# untitled.net
KiCad netlist of a schematic drawn in EAGLE
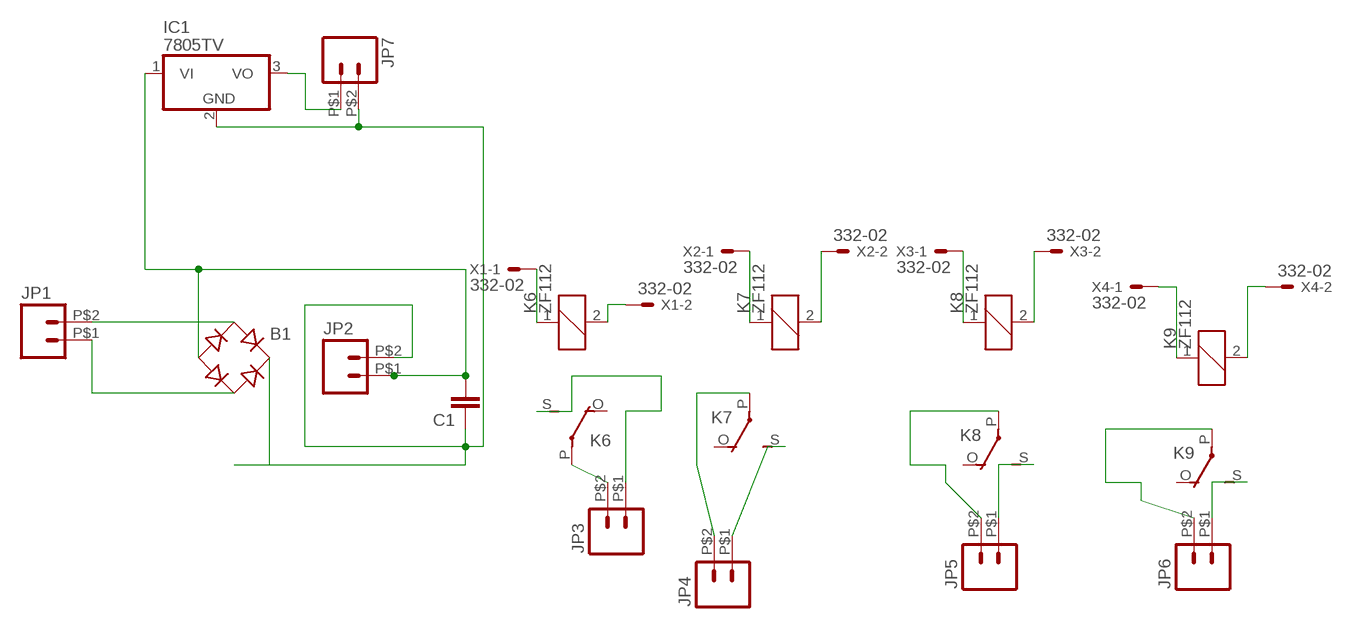
[diagram p0: schematic, sheet 1]

(export (version "E")
  (design (tool "Eeschema 10.0.6"))
  (components
    (comp (ref "B1")
      (value "RB1A")
      (footprint "eagle-import:RB1A")
      (libsource (lib "eagle-import") (part "RB1A"))
    )
    (comp (ref "C1")
      (value "CAPKIT")
      (footprint "eagle-import:CAP-PTH-SMALL-KIT")
      (libsource (lib "eagle-import") (part "CAPKIT"))
    )
    (comp (ref "IC1")
      (value "7805TV")
      (footprint "eagle-import:TO220V")
      (libsource (lib "eagle-import") (part "78TV05"))
    )
    (comp (ref "JP1")
      (value "M02PTH2")
      (footprint "eagle-import:1X02_BIG")
      (libsource (lib "eagle-import") (part "M02PTH2"))
    )
    (comp (ref "JP2")
      (value "M02PTH2")
      (footprint "eagle-import:1X02_BIG")
      (libsource (lib "eagle-import") (part "M02PTH2"))
    )
    (comp (ref "JP3")
      (value "M02PTH2")
      (footprint "eagle-import:1X02_BIG")
      (libsource (lib "eagle-import") (part "M02PTH2"))
    )
    (comp (ref "JP4")
      (value "M02PTH2")
      (footprint "eagle-import:1X02_BIG")
      (libsource (lib "eagle-import") (part "M02PTH2"))
    )
    (comp (ref "JP5")
      (value "M02PTH2")
      (footprint "eagle-import:1X02_BIG")
      (libsource (lib "eagle-import") (part "M02PTH2"))
    )
    (comp (ref "JP6")
      (value "M02PTH2")
      (footprint "eagle-import:1X02_BIG")
      (libsource (lib "eagle-import") (part "M02PTH2"))
    )
    (comp (ref "JP7")
      (value "M02PTH2")
      (footprint "eagle-import:1X02_BIG")
      (libsource (lib "eagle-import") (part "M02PTH2"))
    )
    (comp (ref "K6")
      (value "ZF112")
      (footprint "eagle-import:ZF112")
      (libsource (lib "eagle-import") (part "ZF112"))
    )
    (comp (ref "K7")
      (value "ZF112")
      (footprint "eagle-import:ZF112")
      (libsource (lib "eagle-import") (part "ZF112"))
    )
    (comp (ref "K8")
      (value "ZF112")
      (footprint "eagle-import:ZF112")
      (libsource (lib "eagle-import") (part "ZF112"))
    )
    (comp (ref "K9")
      (value "ZF112")
      (footprint "eagle-import:ZF112")
      (libsource (lib "eagle-import") (part "ZF112"))
    )
    (comp (ref "X1")
      (value "332-02")
      (footprint "eagle-import:332-02")
      (libsource (lib "eagle-import") (part "332-02"))
    )
    (comp (ref "X2")
      (value "332-02")
      (footprint "eagle-import:332-02")
      (libsource (lib "eagle-import") (part "332-02"))
    )
    (comp (ref "X3")
      (value "332-02")
      (footprint "eagle-import:332-02")
      (libsource (lib "eagle-import") (part "332-02"))
    )
    (comp (ref "X4")
      (value "332-02")
      (footprint "eagle-import:332-02")
      (libsource (lib "eagle-import") (part "332-02"))
    )
  )
  (nets
    (net (code "1") (name "Net-(IC1-GND)") (class "Default")
      (node (ref "B1") (pin "+") (pinfunction "+_+") (pintype "passive"))
      (node (ref "C1") (pin "1") (pinfunction "1_1") (pintype "passive"))
      (node (ref "IC1") (pin "2") (pinfunction "GND_2") (pintype "passive"))
      (node (ref "JP2") (pin "P$2") (pinfunction "2_P$2") (pintype "passive"))
      (node (ref "JP7") (pin "P$2") (pinfunction "2_P$2") (pintype "passive"))
    )
    (net (code "2") (name "Net-(IC1-VI)") (class "Default")
      (node (ref "B1") (pin "-") (pinfunction "-_-") (pintype "passive"))
      (node (ref "C1") (pin "2") (pinfunction "2_2") (pintype "passive"))
      (node (ref "IC1") (pin "1") (pinfunction "VI_1") (pintype "input"))
      (node (ref "JP2") (pin "P$1") (pinfunction "1_P$1") (pintype "passive"))
    )
    (net (code "3") (name "Net-(IC1-VO)") (class "Default")
      (node (ref "IC1") (pin "3") (pinfunction "VO_3") (pintype "passive"))
      (node (ref "JP7") (pin "P$1") (pinfunction "1_P$1") (pintype "passive"))
    )
    (net (code "4") (name "Net-(JP1-1)") (class "Default")
      (node (ref "B1") (pin "AC2") (pinfunction "AC2_AC2") (pintype "passive"))
      (node (ref "JP1") (pin "P$1") (pinfunction "1_P$1") (pintype "passive"))
    )
    (net (code "5") (name "Net-(JP1-2)") (class "Default")
      (node (ref "B1") (pin "AC1") (pinfunction "AC1_AC1") (pintype "passive"))
      (node (ref "JP1") (pin "P$2") (pinfunction "2_P$2") (pintype "passive"))
    )
    (net (code "6") (name "Net-(JP3-1)") (class "Default")
      (node (ref "JP3") (pin "P$1") (pinfunction "1_P$1") (pintype "passive"))
      (node (ref "K6") (pin "S") (pinfunction "S_S") (pintype "passive"))
    )
    (net (code "7") (name "Net-(JP3-2)") (class "Default")
      (node (ref "JP3") (pin "P$2") (pinfunction "2_P$2") (pintype "passive"))
      (node (ref "K6") (pin "P") (pinfunction "P_P") (pintype "passive"))
    )
    (net (code "8") (name "Net-(JP4-1)") (class "Default")
      (node (ref "JP4") (pin "P$1") (pinfunction "1_P$1") (pintype "passive"))
      (node (ref "K7") (pin "S") (pinfunction "S_S") (pintype "passive"))
    )
    (net (code "9") (name "Net-(JP4-2)") (class "Default")
      (node (ref "JP4") (pin "P$2") (pinfunction "2_P$2") (pintype "passive"))
      (node (ref "K7") (pin "P") (pinfunction "P_P") (pintype "passive"))
    )
    (net (code "10") (name "Net-(JP5-1)") (class "Default")
      (node (ref "JP5") (pin "P$1") (pinfunction "1_P$1") (pintype "passive"))
      (node (ref "K8") (pin "S") (pinfunction "S_S") (pintype "passive"))
    )
    (net (code "11") (name "Net-(JP5-2)") (class "Default")
      (node (ref "JP5") (pin "P$2") (pinfunction "2_P$2") (pintype "passive"))
      (node (ref "K8") (pin "P") (pinfunction "P_P") (pintype "passive"))
    )
    (net (code "12") (name "Net-(JP6-1)") (class "Default")
      (node (ref "JP6") (pin "P$1") (pinfunction "1_P$1") (pintype "passive"))
      (node (ref "K9") (pin "S") (pinfunction "S_S") (pintype "passive"))
    )
    (net (code "13") (name "Net-(JP6-2)") (class "Default")
      (node (ref "JP6") (pin "P$2") (pinfunction "2_P$2") (pintype "passive"))
      (node (ref "K9") (pin "P") (pinfunction "P_P") (pintype "passive"))
    )
    (net (code "14") (name "Net-(X1A-S)") (class "Default")
      (node (ref "K6") (pin "1") (pinfunction "1_1") (pintype "passive"))
      (node (ref "X1") (pin "1") (pinfunction "S_1") (pintype "passive"))
    )
    (net (code "15") (name "Net-(X1B-S)") (class "Default")
      (node (ref "K6") (pin "2") (pinfunction "2_2") (pintype "passive"))
      (node (ref "X1") (pin "2") (pinfunction "S_2") (pintype "passive"))
    )
    (net (code "16") (name "Net-(X2A-S)") (class "Default")
      (node (ref "K7") (pin "1") (pinfunction "1_1") (pintype "passive"))
      (node (ref "X2") (pin "1") (pinfunction "S_1") (pintype "passive"))
    )
    (net (code "17") (name "Net-(X2B-S)") (class "Default")
      (node (ref "K7") (pin "2") (pinfunction "2_2") (pintype "passive"))
      (node (ref "X2") (pin "2") (pinfunction "S_2") (pintype "passive"))
    )
    (net (code "18") (name "Net-(X3A-S)") (class "Default")
      (node (ref "K8") (pin "1") (pinfunction "1_1") (pintype "passive"))
      (node (ref "X3") (pin "1") (pinfunction "S_1") (pintype "passive"))
    )
    (net (code "19") (name "Net-(X3B-S)") (class "Default")
      (node (ref "K8") (pin "2") (pinfunction "2_2") (pintype "passive"))
      (node (ref "X3") (pin "2") (pinfunction "S_2") (pintype "passive"))
    )
    (net (code "20") (name "Net-(X4A-S)") (class "Default")
      (node (ref "K9") (pin "1") (pinfunction "1_1") (pintype "passive"))
      (node (ref "X4") (pin "1") (pinfunction "S_1") (pintype "passive"))
    )
    (net (code "21") (name "Net-(X4B-S)") (class "Default")
      (node (ref "K9") (pin "2") (pinfunction "2_2") (pintype "passive"))
      (node (ref "X4") (pin "2") (pinfunction "S_2") (pintype "passive"))
    )
    (net (code "22") (name "unconnected-(K6-PadO)") (class "Default")
      (node (ref "K6") (pin "O") (pinfunction "O_O") (pintype "passive"))
    )
    (net (code "23") (name "unconnected-(K7-PadO)") (class "Default")
      (node (ref "K7") (pin "O") (pinfunction "O_O") (pintype "passive"))
    )
    (net (code "24") (name "unconnected-(K8-PadO)") (class "Default")
      (node (ref "K8") (pin "O") (pinfunction "O_O") (pintype "passive"))
    )
    (net (code "25") (name "unconnected-(K9-PadO)") (class "Default")
      (node (ref "K9") (pin "O") (pinfunction "O_O") (pintype "passive"))
    )
  )
)
